# Enclosure_Front_8Gpio.net
KiCad netlist of a schematic drawn in EAGLE
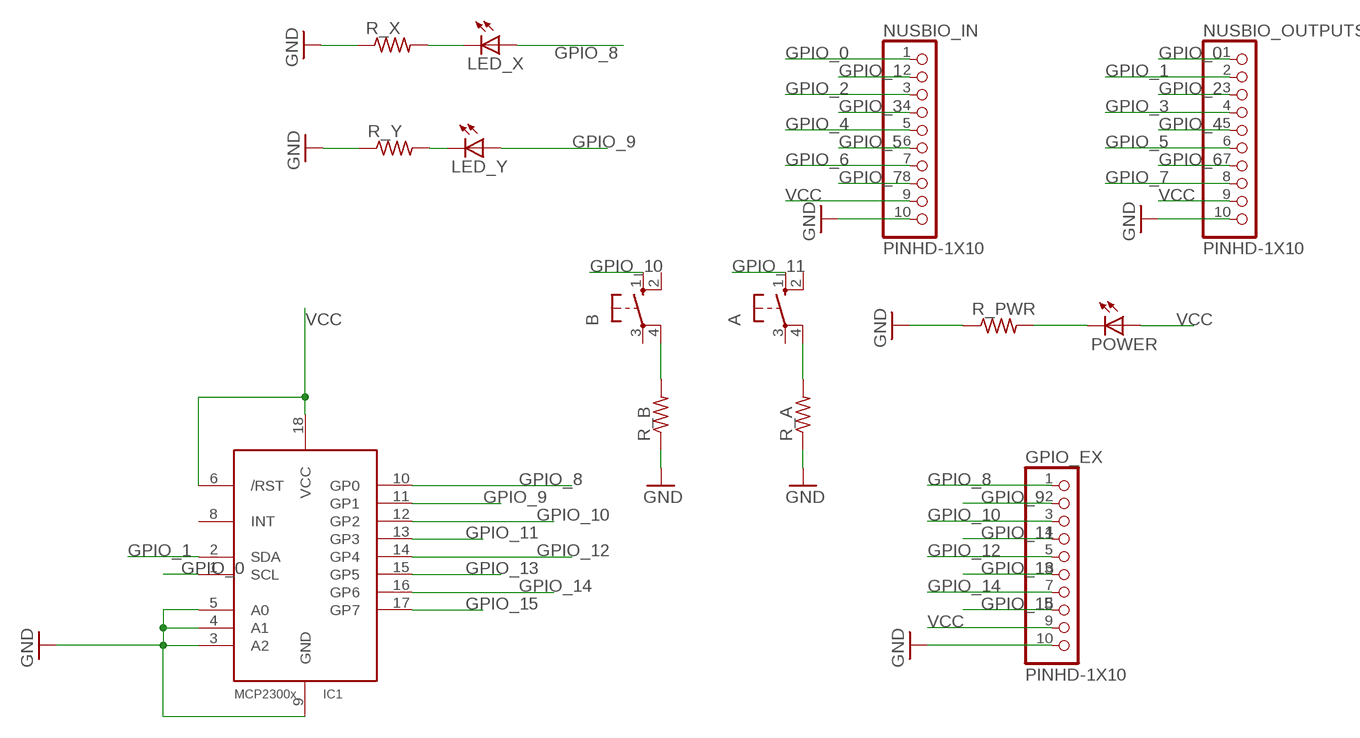
[diagram p0: schematic, sheet 1]

(export (version "E")
  (design (tool "Eeschema 10.0.6"))
  (components
    (comp (ref "A")
      (value "10-XX")
      (footprint "eagle-import:B3F-10XX")
      (fields (field (name "MPN") "B3F-1000"))
      (libsource (lib "eagle-import") (part "10-XX"))
    )
    (comp (ref "B")
      (value "10-XX")
      (footprint "eagle-import:B3F-10XX")
      (fields (field (name "MPN") "B3F-1000"))
      (libsource (lib "eagle-import") (part "10-XX"))
    )
    (comp (ref "GPIO_EX")
      (value "PINHD-1X10")
      (footprint "eagle-import:1X10-BIG")
      (libsource (lib "eagle-import") (part "PINHD-1X10"))
    )
    (comp (ref "IC1")
      (value "MCP23008/SO")
      (footprint "eagle-import:SO18W")
      (libsource (lib "eagle-import") (part "MCP23008/SO"))
    )
    (comp (ref "LED_X")
      (value "LEDSMT1206")
      (footprint "eagle-import:1206")
      (libsource (lib "eagle-import") (part "LEDSMT1206"))
    )
    (comp (ref "LED_Y")
      (value "LEDSMT1206")
      (footprint "eagle-import:1206")
      (libsource (lib "eagle-import") (part "LEDSMT1206"))
    )
    (comp (ref "NUSBIO_IN")
      (value "PINHD-1X10")
      (footprint "eagle-import:1X10-BIG")
      (libsource (lib "eagle-import") (part "PINHD-1X10"))
    )
    (comp (ref "NUSBIO_OUTPUTS")
      (value "PINHD-1X10")
      (footprint "eagle-import:1X10-BIG")
      (libsource (lib "eagle-import") (part "PINHD-1X10"))
    )
    (comp (ref "POWER")
      (value "LEDSMT1206")
      (footprint "eagle-import:1206")
      (libsource (lib "eagle-import") (part "LEDSMT1206"))
    )
    (comp (ref "R_A")
      (value "R-US_R1206")
      (footprint "eagle-import:R1206")
      (libsource (lib "eagle-import") (part "R-US_R1206"))
    )
    (comp (ref "R_B")
      (value "R-US_R1206")
      (footprint "eagle-import:R1206")
      (libsource (lib "eagle-import") (part "R-US_R1206"))
    )
    (comp (ref "R_PWR")
      (value "R-US_R1206")
      (footprint "eagle-import:R1206")
      (libsource (lib "eagle-import") (part "R-US_R1206"))
    )
    (comp (ref "R_X")
      (value "R-US_R1206")
      (footprint "eagle-import:R1206")
      (libsource (lib "eagle-import") (part "R-US_R1206"))
    )
    (comp (ref "R_Y")
      (value "R-US_R1206")
      (footprint "eagle-import:R1206")
      (libsource (lib "eagle-import") (part "R-US_R1206"))
    )
  )
  (nets
    (net (code "1") (name "/GPIO_0") (class "Default")
      (node (ref "IC1") (pin "1") (pinfunction "SCL_1") (pintype "bidirectional"))
      (node (ref "NUSBIO_IN") (pin "1") (pinfunction "1_1") (pintype "passive"))
      (node (ref "NUSBIO_OUTPUTS") (pin "1") (pinfunction "1_1") (pintype "passive"))
    )
    (net (code "2") (name "/GPIO_1") (class "Default")
      (node (ref "IC1") (pin "2") (pinfunction "SDA_2") (pintype "bidirectional"))
      (node (ref "NUSBIO_IN") (pin "2") (pinfunction "2_2") (pintype "passive"))
      (node (ref "NUSBIO_OUTPUTS") (pin "2") (pinfunction "2_2") (pintype "passive"))
    )
    (net (code "3") (name "/GPIO_2") (class "Default")
      (node (ref "NUSBIO_IN") (pin "3") (pinfunction "3_3") (pintype "passive"))
      (node (ref "NUSBIO_OUTPUTS") (pin "3") (pinfunction "3_3") (pintype "passive"))
    )
    (net (code "4") (name "/GPIO_3") (class "Default")
      (node (ref "NUSBIO_IN") (pin "4") (pinfunction "4_4") (pintype "passive"))
      (node (ref "NUSBIO_OUTPUTS") (pin "4") (pinfunction "4_4") (pintype "passive"))
    )
    (net (code "5") (name "/GPIO_4") (class "Default")
      (node (ref "NUSBIO_IN") (pin "5") (pinfunction "5_5") (pintype "passive"))
      (node (ref "NUSBIO_OUTPUTS") (pin "5") (pinfunction "5_5") (pintype "passive"))
    )
    (net (code "6") (name "/GPIO_5") (class "Default")
      (node (ref "NUSBIO_IN") (pin "6") (pinfunction "6_6") (pintype "passive"))
      (node (ref "NUSBIO_OUTPUTS") (pin "6") (pinfunction "6_6") (pintype "passive"))
    )
    (net (code "7") (name "/GPIO_6") (class "Default")
      (node (ref "NUSBIO_IN") (pin "7") (pinfunction "7_7") (pintype "passive"))
      (node (ref "NUSBIO_OUTPUTS") (pin "7") (pinfunction "7_7") (pintype "passive"))
    )
    (net (code "8") (name "/GPIO_7") (class "Default")
      (node (ref "NUSBIO_IN") (pin "8") (pinfunction "8_8") (pintype "passive"))
      (node (ref "NUSBIO_OUTPUTS") (pin "8") (pinfunction "8_8") (pintype "passive"))
    )
    (net (code "9") (name "/GPIO_8") (class "Default")
      (node (ref "GPIO_EX") (pin "1") (pinfunction "1_1") (pintype "passive"))
      (node (ref "IC1") (pin "10") (pinfunction "GP0_10") (pintype "bidirectional"))
      (node (ref "LED_X") (pin "A") (pinfunction "A_A") (pintype "passive"))
    )
    (net (code "10") (name "/GPIO_9") (class "Default")
      (node (ref "GPIO_EX") (pin "2") (pinfunction "2_2") (pintype "passive"))
      (node (ref "IC1") (pin "11") (pinfunction "GP1_11") (pintype "bidirectional"))
      (node (ref "LED_Y") (pin "A") (pinfunction "A_A") (pintype "passive"))
    )
    (net (code "11") (name "/GPIO_10") (class "Default")
      (node (ref "B") (pin "1") (pinfunction "S_1") (pintype "passive"))
      (node (ref "GPIO_EX") (pin "3") (pinfunction "3_3") (pintype "passive"))
      (node (ref "IC1") (pin "12") (pinfunction "GP2_12") (pintype "bidirectional"))
    )
    (net (code "12") (name "/GPIO_11") (class "Default")
      (node (ref "A") (pin "1") (pinfunction "S_1") (pintype "passive"))
      (node (ref "GPIO_EX") (pin "4") (pinfunction "4_4") (pintype "passive"))
      (node (ref "IC1") (pin "13") (pinfunction "GP3_13") (pintype "bidirectional"))
    )
    (net (code "13") (name "/GPIO_12") (class "Default")
      (node (ref "GPIO_EX") (pin "5") (pinfunction "5_5") (pintype "passive"))
      (node (ref "IC1") (pin "14") (pinfunction "GP4_14") (pintype "bidirectional"))
    )
    (net (code "14") (name "/GPIO_13") (class "Default")
      (node (ref "GPIO_EX") (pin "6") (pinfunction "6_6") (pintype "passive"))
      (node (ref "IC1") (pin "15") (pinfunction "GP5_15") (pintype "bidirectional"))
    )
    (net (code "15") (name "/GPIO_14") (class "Default")
      (node (ref "GPIO_EX") (pin "7") (pinfunction "7_7") (pintype "passive"))
      (node (ref "IC1") (pin "16") (pinfunction "GP6_16") (pintype "bidirectional"))
    )
    (net (code "16") (name "/GPIO_15") (class "Default")
      (node (ref "GPIO_EX") (pin "8") (pinfunction "8_8") (pintype "passive"))
      (node (ref "IC1") (pin "17") (pinfunction "GP7_17") (pintype "bidirectional"))
    )
    (net (code "17") (name "/VCC") (class "Default")
      (node (ref "GPIO_EX") (pin "9") (pinfunction "9_9") (pintype "passive"))
      (node (ref "IC1") (pin "18") (pinfunction "VCC_18") (pintype "power_in"))
      (node (ref "IC1") (pin "6") (pinfunction "/RST_6") (pintype "input"))
      (node (ref "NUSBIO_IN") (pin "9") (pinfunction "9_9") (pintype "passive"))
      (node (ref "NUSBIO_OUTPUTS") (pin "9") (pinfunction "9_9") (pintype "passive"))
      (node (ref "POWER") (pin "A") (pinfunction "A_A") (pintype "passive"))
    )
    (net (code "18") (name "GND") (class "Default")
      (node (ref "GPIO_EX") (pin "10") (pinfunction "10_10") (pintype "passive"))
      (node (ref "IC1") (pin "3") (pinfunction "A2_3") (pintype "input"))
      (node (ref "IC1") (pin "4") (pinfunction "A1_4") (pintype "input"))
      (node (ref "IC1") (pin "5") (pinfunction "A0_5") (pintype "input"))
      (node (ref "IC1") (pin "9") (pinfunction "GND_9") (pintype "power_in"))
      (node (ref "NUSBIO_IN") (pin "10") (pinfunction "10_10") (pintype "passive"))
      (node (ref "NUSBIO_OUTPUTS") (pin "10") (pinfunction "10_10") (pintype "passive"))
      (node (ref "R_A") (pin "1") (pinfunction "1_1") (pintype "passive"))
      (node (ref "R_B") (pin "1") (pinfunction "1_1") (pintype "passive"))
      (node (ref "R_PWR") (pin "1") (pinfunction "1_1") (pintype "passive"))
      (node (ref "R_X") (pin "1") (pinfunction "1_1") (pintype "passive"))
      (node (ref "R_Y") (pin "1") (pinfunction "1_1") (pintype "passive"))
    )
    (net (code "19") (name "Net-(A-P1)") (class "Default")
      (node (ref "A") (pin "4") (pinfunction "P1_4") (pintype "passive"))
      (node (ref "R_A") (pin "2") (pinfunction "2_2") (pintype "passive"))
    )
    (net (code "20") (name "Net-(B-P1)") (class "Default")
      (node (ref "B") (pin "4") (pinfunction "P1_4") (pintype "passive"))
      (node (ref "R_B") (pin "2") (pinfunction "2_2") (pintype "passive"))
    )
    (net (code "21") (name "Net-(LED_X-PadC)") (class "Default")
      (node (ref "LED_X") (pin "C") (pinfunction "C_C") (pintype "passive"))
      (node (ref "R_X") (pin "2") (pinfunction "2_2") (pintype "passive"))
    )
    (net (code "22") (name "Net-(LED_Y-PadC)") (class "Default")
      (node (ref "LED_Y") (pin "C") (pinfunction "C_C") (pintype "passive"))
      (node (ref "R_Y") (pin "2") (pinfunction "2_2") (pintype "passive"))
    )
    (net (code "23") (name "Net-(POWER-PadC)") (class "Default")
      (node (ref "POWER") (pin "C") (pinfunction "C_C") (pintype "passive"))
      (node (ref "R_PWR") (pin "2") (pinfunction "2_2") (pintype "passive"))
    )
    (net (code "24") (name "unconnected-(A-P-Pad3)") (class "Default")
      (node (ref "A") (pin "3") (pinfunction "P_3") (pintype "passive"))
    )
    (net (code "25") (name "unconnected-(A-S1-Pad2)") (class "Default")
      (node (ref "A") (pin "2") (pinfunction "S1_2") (pintype "passive"))
    )
    (net (code "26") (name "unconnected-(B-P-Pad3)") (class "Default")
      (node (ref "B") (pin "3") (pinfunction "P_3") (pintype "passive"))
    )
    (net (code "27") (name "unconnected-(B-S1-Pad2)") (class "Default")
      (node (ref "B") (pin "2") (pinfunction "S1_2") (pintype "passive"))
    )
    (net (code "28") (name "unconnected-(IC1-INT-Pad8)") (class "Default")
      (node (ref "IC1") (pin "8") (pinfunction "INT_8") (pintype "output"))
    )
  )
)
